# control_connector.net
KiCad netlist of a schematic drawn in Altium Designer
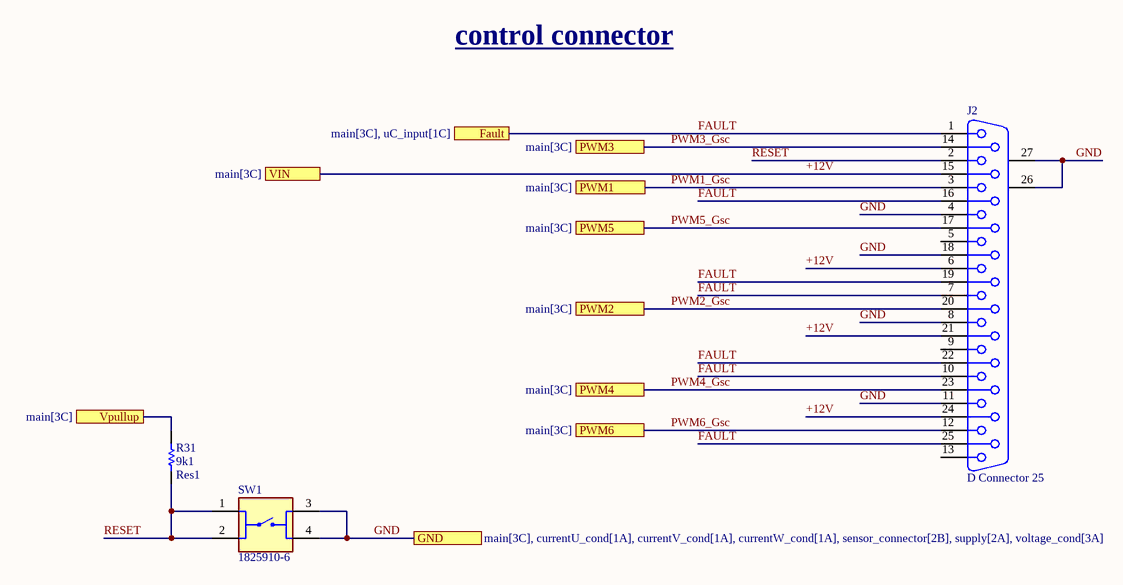
[diagram p0: control_connector.SchDoc]

(export (version "E")
  (design (tool "Eeschema 10.0.6"))
  (components
    (comp (ref "J2")
      (value "D Connector 25")
      (footprint "DSUB1.385-2H25A_mod")
      (description "Receptacle Assembly, 25 Position, Right Angle")
      (fields (field (name "PUBLISHER") "Altium Limited"))
      (libsource (lib "LABSTEPS_Project") (part "D Connector 25"))
    )
    (comp (ref "R31")
      (value "Res1")
      (footprint "AXIAL-0.3_mod")
      (description "Resistor")
      (fields (field (name "ALTIUM_VALUE") "9k1") (field (name "PUBLISHER") "Altium Limited"))
      (libsource (lib "LABSTEPS_Project") (part "Res1"))
    )
    (comp (ref "SW1")
      (value "1825910-6")
      (footprint "SW_1825910-6-4_mod")
      (description "Switch Push Button OFF (ON) SPST Round Button 0.05A 24VDC Momentary Contact PC Pins Thru-Hole")
      (fields (field (name "MF") "TE Connectivity") (field (name "DIGI-KEY_PART_NUMBER") "450-1650-ND"))
      (libsource (lib "SW_1825910-6-4") (part "1825910-6"))
    )
  )
  (nets
    (net (code "1") (name "/+12V") (class "Default")
      (node (ref "J2") (pin "15") (pinfunction "15_15") (pintype "passive"))
      (node (ref "J2") (pin "21") (pinfunction "21_21") (pintype "passive"))
      (node (ref "J2") (pin "24") (pinfunction "24_24") (pintype "passive"))
      (node (ref "J2") (pin "6") (pinfunction "6_6") (pintype "passive"))
    )
    (net (code "2") (name "/FAULT") (class "Default")
      (node (ref "J2") (pin "1") (pinfunction "1_1") (pintype "passive"))
      (node (ref "J2") (pin "10") (pinfunction "10_10") (pintype "passive"))
      (node (ref "J2") (pin "16") (pinfunction "16_16") (pintype "passive"))
      (node (ref "J2") (pin "19") (pinfunction "19_19") (pintype "passive"))
      (node (ref "J2") (pin "22") (pinfunction "22_22") (pintype "passive"))
      (node (ref "J2") (pin "25") (pinfunction "25_25") (pintype "passive"))
      (node (ref "J2") (pin "7") (pinfunction "7_7") (pintype "passive"))
    )
    (net (code "3") (name "/GND") (class "Default")
      (node (ref "J2") (pin "11") (pinfunction "11_11") (pintype "passive"))
      (node (ref "J2") (pin "18") (pinfunction "18_18") (pintype "passive"))
      (node (ref "J2") (pin "26") (pinfunction "MH1_26") (pintype "passive"))
      (node (ref "J2") (pin "27") (pinfunction "MH2_27") (pintype "passive"))
      (node (ref "J2") (pin "4") (pinfunction "4_4") (pintype "passive"))
      (node (ref "J2") (pin "8") (pinfunction "8_8") (pintype "passive"))
      (node (ref "SW1") (pin "3") (pinfunction "3_3") (pintype "passive"))
      (node (ref "SW1") (pin "4") (pinfunction "4_4") (pintype "passive"))
    )
    (net (code "4") (name "/PWM1_Gsc") (class "Default")
      (node (ref "J2") (pin "3") (pinfunction "3_3") (pintype "passive"))
    )
    (net (code "5") (name "/PWM2_Gsc") (class "Default")
      (node (ref "J2") (pin "20") (pinfunction "20_20") (pintype "passive"))
    )
    (net (code "6") (name "/PWM3_Gsc") (class "Default")
      (node (ref "J2") (pin "14") (pinfunction "14_14") (pintype "passive"))
    )
    (net (code "7") (name "/PWM4_Gsc") (class "Default")
      (node (ref "J2") (pin "23") (pinfunction "23_23") (pintype "passive"))
    )
    (net (code "8") (name "/PWM5_Gsc") (class "Default")
      (node (ref "J2") (pin "17") (pinfunction "17_17") (pintype "passive"))
    )
    (net (code "9") (name "/PWM6_Gsc") (class "Default")
      (node (ref "J2") (pin "12") (pinfunction "12_12") (pintype "passive"))
    )
    (net (code "10") (name "/RESET") (class "Default")
      (node (ref "J2") (pin "2") (pinfunction "2_2") (pintype "passive"))
      (node (ref "R31") (pin "1") (pinfunction "1_1") (pintype "passive"))
      (node (ref "SW1") (pin "1") (pinfunction "1_1") (pintype "passive"))
      (node (ref "SW1") (pin "2") (pinfunction "2_2") (pintype "passive"))
    )
    (net (code "11") (name "/Vpullup") (class "Default")
      (node (ref "R31") (pin "2") (pinfunction "2_2") (pintype "passive"))
    )
    (net (code "12") (name "unconnected-(J2-Pad5)") (class "Default")
      (node (ref "J2") (pin "5") (pinfunction "5_5") (pintype "passive"))
    )
    (net (code "13") (name "unconnected-(J2-Pad9)") (class "Default")
      (node (ref "J2") (pin "9") (pinfunction "9_9") (pintype "passive"))
    )
    (net (code "14") (name "unconnected-(J2-Pad13)") (class "Default")
      (node (ref "J2") (pin "13") (pinfunction "13_13") (pintype "passive"))
    )
  )
)
